# RFR24_AMS_Design_-_EEPROM_V1.net
KiCad netlist of a schematic drawn in Altium Designer
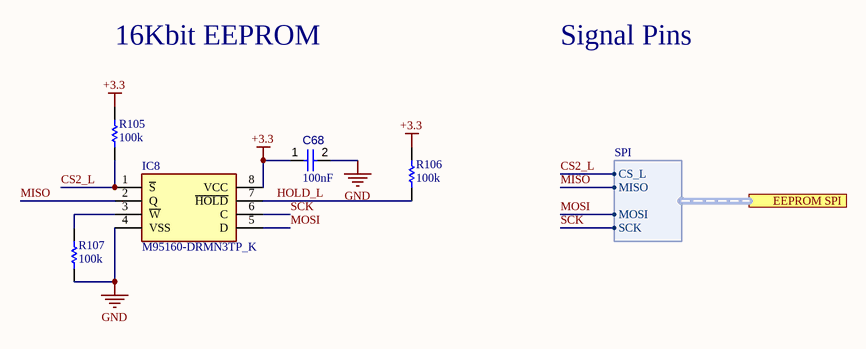
[diagram p0: RFR24 AMS Design - EEPROM V1.SchDoc]

(export (version "E")
  (design (tool "Eeschema 10.0.6"))
  (components
    (comp (ref "C68")
      (value "100nF")
      (footprint "CAPC2013X145X50LL20T25")
      (description "Chip Capacitor, 1 uF, +/-10%, 25 V, 0805 (2012 Metric)")
      (fields (field (name "TOLERANCE") "10%") (field (name "Comment") "Capacitor 1 uF +/- 10% 25 V 0805"))
      (libsource (lib "Rutgers University") (part "CAP-NP-2"))
    )
    (comp (ref "IC8")
      (value "M95160-DRMN3TP_K")
      (footprint "SamacSys:SOIC127P600X175-8N")
      (description "Integrated Circuit")
      (fields
        (field (name "MANUFACTURER_PART_NUMBER") "M95160-DRMN3TP/K")
        (field (name "MOUSER PART NUMBER") "511-M95160-DRMN3TP/K")
      )
      (libsource (lib "*") (part "M95160-DRMN3TP_K"))
    )
    (comp (ref "R105")
      (value "100k")
      (footprint "RESC2013X70X40LL20T20")
      (description "Chip Resistor, 1 KOhm, +/- 1%, 0.125 W, -55 to 155 degC, 0805 (2013 Metric)")
      (fields (field (name "TOLERANCE") "1%") (field (name "POWER") "125mW"))
      (libsource (lib "Rutgers University") (part "RES-2"))
    )
    (comp (ref "R106")
      (value "100k")
      (footprint "RESC2013X70X40LL20T20")
      (description "Chip Resistor, 1 KOhm, +/- 1%, 0.125 W, -55 to 155 degC, 0805 (2013 Metric)")
      (fields (field (name "TOLERANCE") "1%") (field (name "POWER") "125mW"))
      (libsource (lib "Rutgers University") (part "RES-2"))
    )
    (comp (ref "R107")
      (value "100k")
      (footprint "RESC2013X70X40LL20T20")
      (description "Chip Resistor, 1 KOhm, +/- 1%, 0.125 W, -55 to 155 degC, 0805 (2013 Metric)")
      (fields (field (name "TOLERANCE") "1%") (field (name "POWER") "125mW"))
      (libsource (lib "Rutgers University") (part "RES-2"))
    )
  )
  (nets
    (net (code "2") (name "+3.3") (class "Default")
      (node (ref "C68") (pin "1") (pinfunction "1_1") (pintype "passive"))
      (node (ref "IC8") (pin "8") (pinfunction "VCC_8") (pintype "passive"))
      (node (ref "R105") (pin "2") (pinfunction "2_2") (pintype "passive"))
      (node (ref "R106") (pin "2") (pinfunction "2_2") (pintype "passive"))
    )
    (net (code "3") (name "/CS2_L") (class "Default")
      (node (ref "IC8") (pin "1") (pinfunction "~{S}_1") (pintype "passive"))
      (node (ref "R105") (pin "1") (pinfunction "1_1") (pintype "passive"))
    )
    (net (code "4") (name "/HOLD_L") (class "Default")
      (node (ref "IC8") (pin "7") (pinfunction "~{HOLD}_7") (pintype "passive"))
      (node (ref "R106") (pin "1") (pinfunction "1_1") (pintype "passive"))
    )
    (net (code "5") (name "/MISO") (class "Default")
      (node (ref "IC8") (pin "2") (pinfunction "Q_2") (pintype "passive"))
    )
    (net (code "6") (name "/MOSI") (class "Default")
      (node (ref "IC8") (pin "5") (pinfunction "D_5") (pintype "passive"))
    )
    (net (code "7") (name "/SCK") (class "Default")
      (node (ref "IC8") (pin "6") (pinfunction "C_6") (pintype "passive"))
    )
    (net (code "9") (name "GND") (class "Default")
      (node (ref "C68") (pin "2") (pinfunction "2_2") (pintype "passive"))
      (node (ref "IC8") (pin "4") (pinfunction "VSS_4") (pintype "passive"))
      (node (ref "R107") (pin "1") (pinfunction "1_1") (pintype "passive"))
    )
    (net (code "10") (name "Net-(IC8-~{W})") (class "Default")
      (node (ref "IC8") (pin "3") (pinfunction "~{W}_3") (pintype "passive"))
      (node (ref "R107") (pin "2") (pinfunction "2_2") (pintype "passive"))
    )
  )
)
